# HenHouseSensorBoard.net
KiCad netlist of a schematic drawn in EAGLE
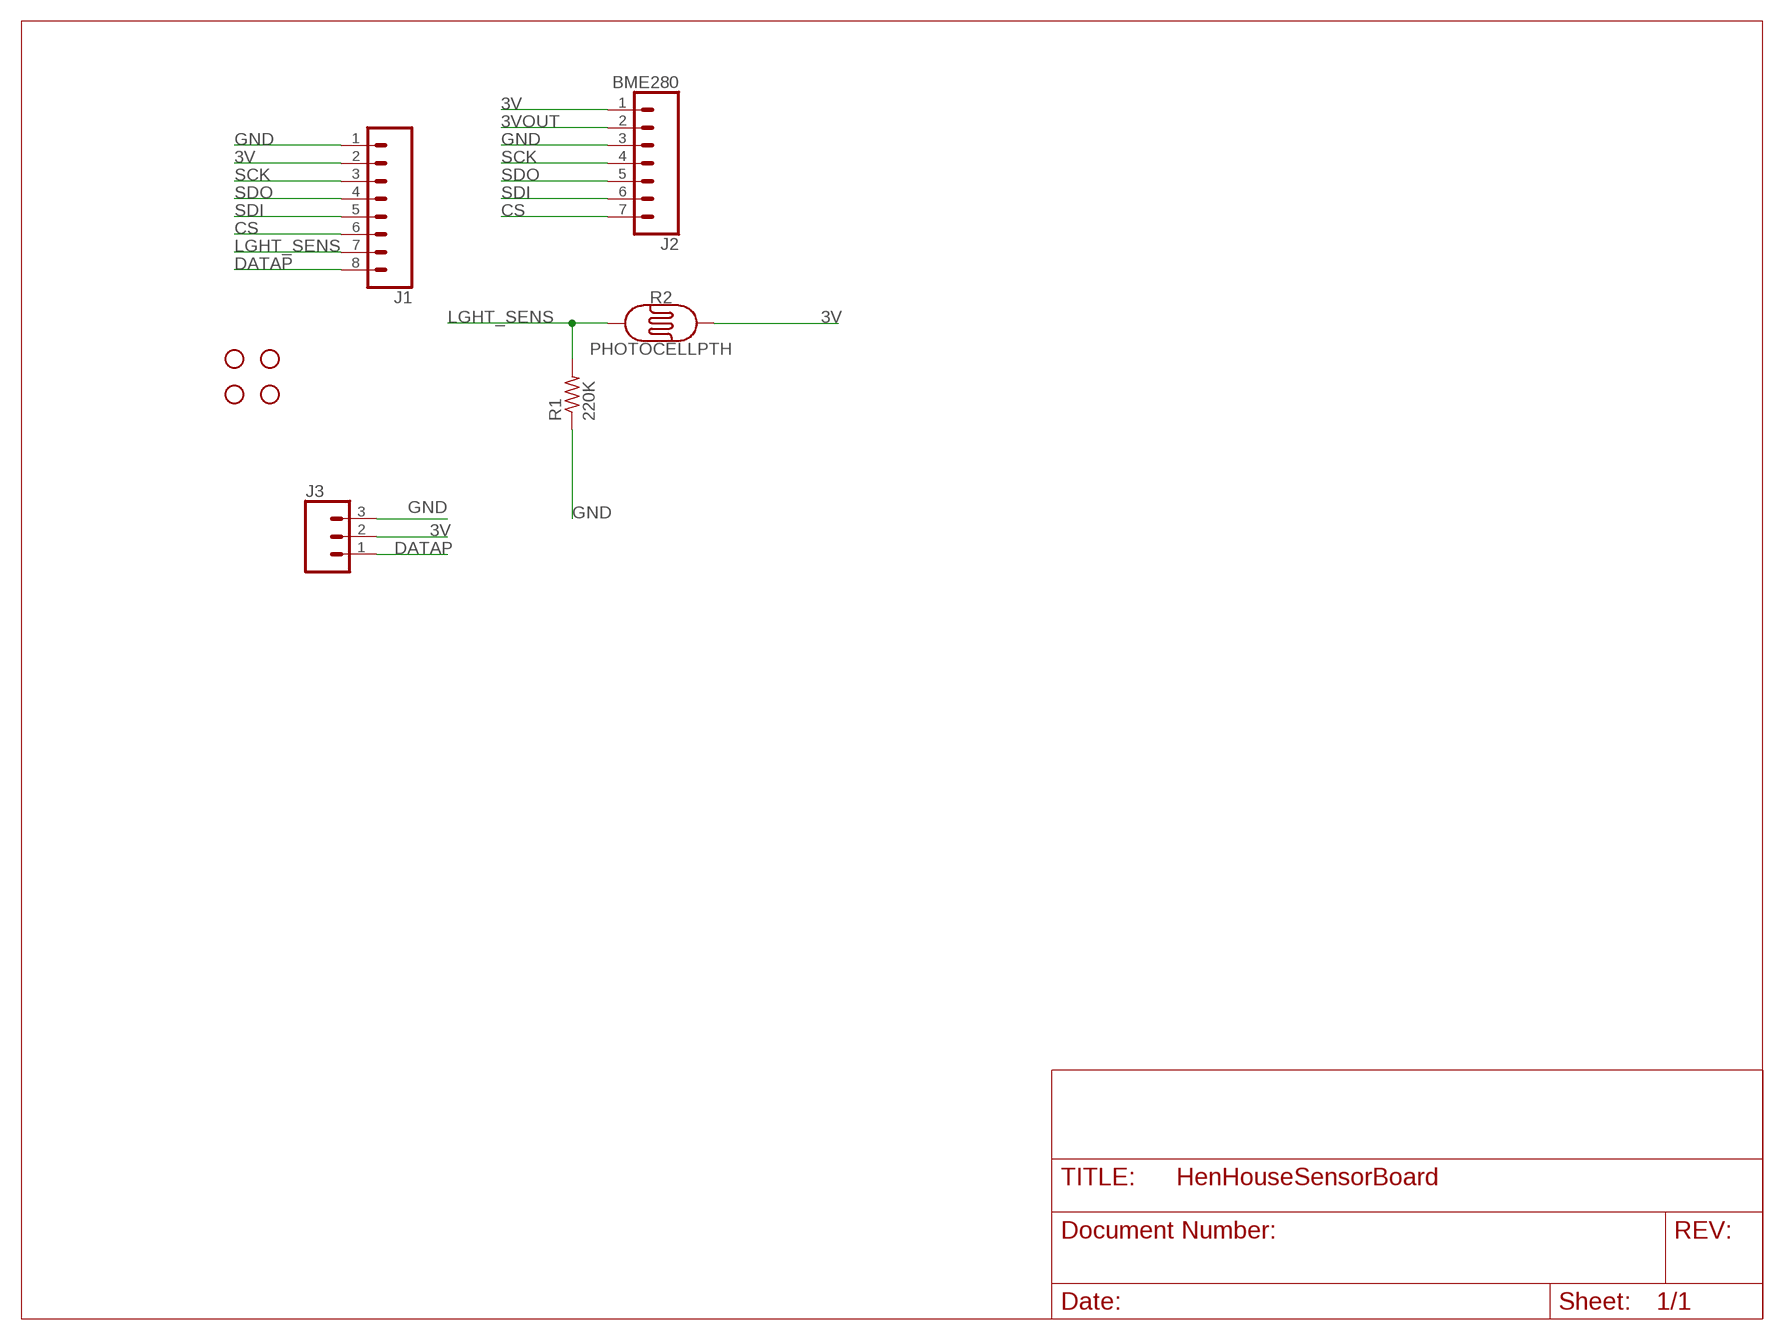
[diagram p0: schematic, sheet 1]

(export (version "E")
  (design (tool "Eeschema 10.0.6"))
  (components
    (comp (ref "H1")
      (value "STAND-OFF")
      (footprint "eagle-import:STAND-OFF")
      (libsource (lib "eagle-import") (part "STAND-OFF"))
    )
    (comp (ref "H2")
      (value "STAND-OFF")
      (footprint "eagle-import:STAND-OFF")
      (libsource (lib "eagle-import") (part "STAND-OFF"))
    )
    (comp (ref "H3")
      (value "STAND-OFF")
      (footprint "eagle-import:STAND-OFF")
      (libsource (lib "eagle-import") (part "STAND-OFF"))
    )
    (comp (ref "H4")
      (value "STAND-OFF")
      (footprint "eagle-import:STAND-OFF")
      (libsource (lib "eagle-import") (part "STAND-OFF"))
    )
    (comp (ref "J1")
      (value "CONN_08LONGPADS")
      (footprint "eagle-import:1X08_LONGPADS")
      (libsource (lib "eagle-import") (part "CONN_08LONGPADS"))
    )
    (comp (ref "J2")
      (value "BME280")
      (footprint "eagle-import:1X07_LONGPADS")
      (libsource (lib "eagle-import") (part "CONN_07LONGPADS"))
    )
    (comp (ref "J3")
      (value "CONN_03LONGPADS")
      (footprint "eagle-import:1X03_LONGPADS")
      (libsource (lib "eagle-import") (part "CONN_03LONGPADS"))
    )
    (comp (ref "R1")
      (value "220K")
      (footprint "eagle-import:0207_9")
      (libsource (lib "eagle-import") (part "R-US_0207/9"))
    )
    (comp (ref "R2")
      (value "PHOTOCELLPTH")
      (footprint "eagle-import:PHOTOCELL")
      (libsource (lib "eagle-import") (part "PHOTOCELLPTH"))
    )
  )
  (nets
    (net (code "1") (name "/3V") (class "Default")
      (node (ref "J1") (pin "2") (pinfunction "2_2") (pintype "passive"))
      (node (ref "J2") (pin "1") (pinfunction "1_1") (pintype "passive"))
      (node (ref "J3") (pin "2") (pinfunction "2_2") (pintype "passive"))
      (node (ref "R2") (pin "2") (pinfunction "P$2_2") (pintype "bidirectional"))
    )
    (net (code "2") (name "/3VOUT") (class "Default")
      (node (ref "J2") (pin "2") (pinfunction "2_2") (pintype "passive"))
    )
    (net (code "3") (name "/CS") (class "Default")
      (node (ref "J1") (pin "6") (pinfunction "6_6") (pintype "passive"))
      (node (ref "J2") (pin "7") (pinfunction "7_7") (pintype "passive"))
    )
    (net (code "4") (name "/DATAP") (class "Default")
      (node (ref "J1") (pin "8") (pinfunction "8_8") (pintype "passive"))
      (node (ref "J3") (pin "1") (pinfunction "1_1") (pintype "passive"))
    )
    (net (code "5") (name "/GND") (class "Default")
      (node (ref "J1") (pin "1") (pinfunction "1_1") (pintype "passive"))
      (node (ref "J2") (pin "3") (pinfunction "3_3") (pintype "passive"))
      (node (ref "J3") (pin "3") (pinfunction "3_3") (pintype "passive"))
      (node (ref "R1") (pin "1") (pinfunction "1_1") (pintype "passive"))
    )
    (net (code "6") (name "/LGHT_SENS") (class "Default")
      (node (ref "J1") (pin "7") (pinfunction "7_7") (pintype "passive"))
      (node (ref "R1") (pin "2") (pinfunction "2_2") (pintype "passive"))
      (node (ref "R2") (pin "1") (pinfunction "P$1_1") (pintype "bidirectional"))
    )
    (net (code "7") (name "/SCK") (class "Default")
      (node (ref "J1") (pin "3") (pinfunction "3_3") (pintype "passive"))
      (node (ref "J2") (pin "4") (pinfunction "4_4") (pintype "passive"))
    )
    (net (code "8") (name "/SDI") (class "Default")
      (node (ref "J1") (pin "5") (pinfunction "5_5") (pintype "passive"))
      (node (ref "J2") (pin "6") (pinfunction "6_6") (pintype "passive"))
    )
    (net (code "9") (name "/SDO") (class "Default")
      (node (ref "J1") (pin "4") (pinfunction "4_4") (pintype "passive"))
      (node (ref "J2") (pin "5") (pinfunction "5_5") (pintype "passive"))
    )
  )
)
